# reading-game.net
KiCad netlist of a schematic drawn in EasyEDA
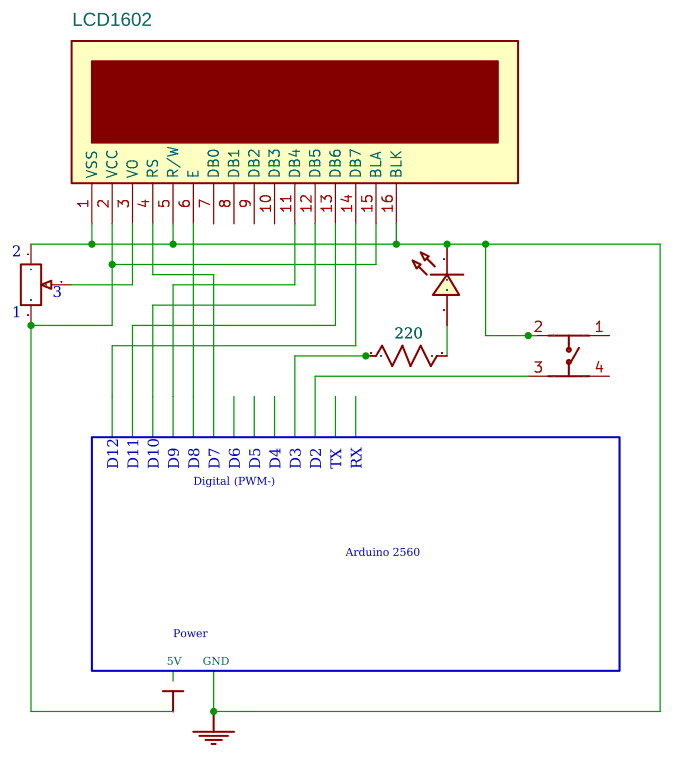
[diagram p0: schematic sheet]

(export (version "E")
  (design (tool "Eeschema 10.0.6"))
  (components
    (comp (ref "KEY1")
      (value "button6*6*8")
      (fields (field (name "BOM_Supplier Part") "C59982"))
      (libsource (lib "") (part "button6*6*8"))
    )
    (comp (ref "LCD1")
      (value "LCD1602")
      (fields
        (field (name "BOM_Manufacturer Part") "LCM1602K-NSW-BBW")
        (field (name "BOM_Supplier Part") "C83275")
      )
      (libsource (lib "") (part "LCD1602"))
    )
    (comp (ref "LED1")
      (value "LED-0603_R")
      (fields
        (field (name "BOM_Manufacturer Part") "19-217/R6C-AL1M2VY/3T")
        (field (name "BOM_Supplier Part") "C72044")
      )
      (libsource (lib "") (part "LED-0603_R"))
    )
    (comp (ref "R1") (value "220") (libsource (lib "") (part "R_0603_US")))
    (comp (ref "RP1") (value "R_3386P_EU") (libsource (lib "") (part "R_3386P_EU")))
  )
  (nets
    (net (code "1") (name "5V") (class "Default")
      (node (ref "LCD1") (pin "15") (pinfunction "BLA_15") (pintype "unspecified"))
      (node (ref "LCD1") (pin "2") (pinfunction "VCC_2") (pintype "unspecified"))
      (node (ref "RP1") (pin "3") (pinfunction "3_3") (pintype "input"))
    )
    (net (code "2") (name "GND") (class "Default")
      (node (ref "KEY1") (pin "2") (pinfunction "2_2") (pintype "unspecified"))
      (node (ref "LCD1") (pin "1") (pinfunction "VSS_1") (pintype "unspecified"))
      (node (ref "LCD1") (pin "16") (pinfunction "BLK_16") (pintype "unspecified"))
      (node (ref "LCD1") (pin "5") (pinfunction "R/W_5") (pintype "unspecified"))
      (node (ref "LED1") (pin "2") (pinfunction "2_2") (pintype "unspecified"))
      (node (ref "RP1") (pin "1") (pinfunction "1_1") (pintype "input"))
    )
    (net (code "3") (name "Net-(LCD1-VO)") (class "Default")
      (node (ref "LCD1") (pin "3") (pinfunction "VO_3") (pintype "unspecified"))
      (node (ref "RP1") (pin "2") (pinfunction "2_2") (pintype "input"))
    )
    (net (code "4") (name "Net-(LED1-Pad1)") (class "Default")
      (node (ref "LED1") (pin "1") (pinfunction "1_1") (pintype "unspecified"))
      (node (ref "R1") (pin "2") (pinfunction "2_2") (pintype "unspecified"))
    )
    (net (code "5") (name "unconnected-(KEY1-Pad1)") (class "Default")
      (node (ref "KEY1") (pin "1") (pinfunction "1_1") (pintype "unspecified"))
    )
    (net (code "6") (name "unconnected-(KEY1-Pad3)") (class "Default")
      (node (ref "KEY1") (pin "3") (pinfunction "3_3") (pintype "unspecified"))
    )
    (net (code "7") (name "unconnected-(KEY1-Pad4)") (class "Default")
      (node (ref "KEY1") (pin "4") (pinfunction "4_4") (pintype "unspecified"))
    )
    (net (code "8") (name "unconnected-(LCD1-DB0-Pad7)") (class "Default")
      (node (ref "LCD1") (pin "7") (pinfunction "DB0_7") (pintype "unspecified"))
    )
    (net (code "9") (name "unconnected-(LCD1-DB1-Pad8)") (class "Default")
      (node (ref "LCD1") (pin "8") (pinfunction "DB1_8") (pintype "unspecified"))
    )
    (net (code "10") (name "unconnected-(LCD1-DB2-Pad9)") (class "Default")
      (node (ref "LCD1") (pin "9") (pinfunction "DB2_9") (pintype "unspecified"))
    )
    (net (code "11") (name "unconnected-(LCD1-DB3-Pad10)") (class "Default")
      (node (ref "LCD1") (pin "10") (pinfunction "DB3_10") (pintype "unspecified"))
    )
    (net (code "12") (name "unconnected-(LCD1-DB4-Pad11)") (class "Default")
      (node (ref "LCD1") (pin "11") (pinfunction "DB4_11") (pintype "unspecified"))
    )
    (net (code "13") (name "unconnected-(LCD1-DB5-Pad12)") (class "Default")
      (node (ref "LCD1") (pin "12") (pinfunction "DB5_12") (pintype "unspecified"))
    )
    (net (code "14") (name "unconnected-(LCD1-DB6-Pad13)") (class "Default")
      (node (ref "LCD1") (pin "13") (pinfunction "DB6_13") (pintype "unspecified"))
    )
    (net (code "15") (name "unconnected-(LCD1-DB7-Pad14)") (class "Default")
      (node (ref "LCD1") (pin "14") (pinfunction "DB7_14") (pintype "unspecified"))
    )
    (net (code "16") (name "unconnected-(LCD1-E-Pad6)") (class "Default")
      (node (ref "LCD1") (pin "6") (pinfunction "E_6") (pintype "unspecified"))
    )
    (net (code "17") (name "unconnected-(LCD1-RS-Pad4)") (class "Default")
      (node (ref "LCD1") (pin "4") (pinfunction "RS_4") (pintype "unspecified"))
    )
    (net (code "18") (name "unconnected-(R1-Pad1)") (class "Default")
      (node (ref "R1") (pin "1") (pinfunction "1_1") (pintype "unspecified"))
    )
  )
)
